# lvds_transceiver.net
KiCad netlist of a schematic drawn in Altium Designer
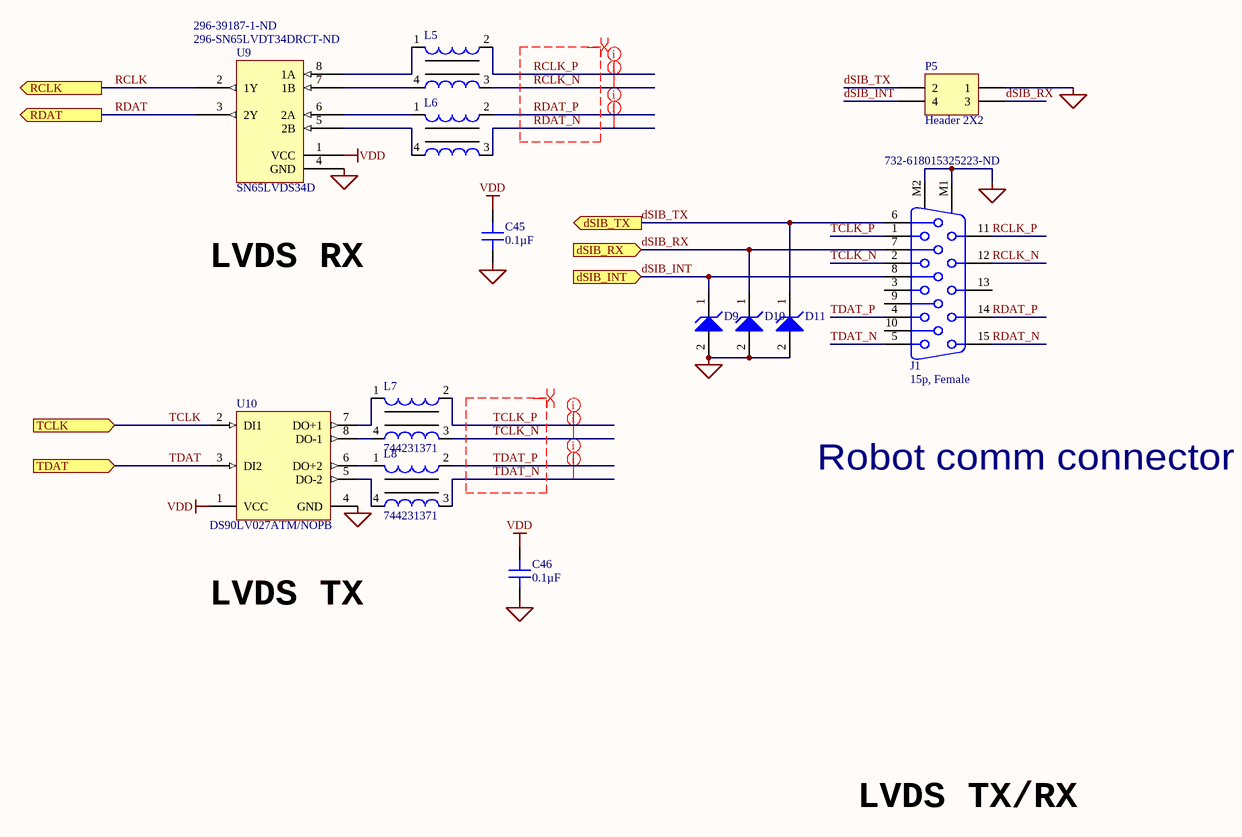
[diagram p0: lvds_transceiver.SchDoc]

(export (version "E")
  (design (tool "Eeschema 10.0.6"))
  (components
    (comp (ref "C45")
      (value "0.1µF")
      (footprint "FP-GRM155-0_05-IPC_B")
      (description "CAP CER 0.1UF 25V X7R 0402")
      (fields (field (name "PART NUMBER") "04023C104KAT2A") (field (name "MANUFACTURER") "AVX Corporation"))
      (libsource (lib "Celestial Altium Library - altium_library") (part "Capacitor"))
    )
    (comp (ref "C46")
      (value "0.1µF")
      (footprint "FP-GRM155-0_05-IPC_B")
      (description "CAP CER 0.1UF 25V X7R 0402")
      (fields (field (name "PART NUMBER") "04023C104KAT2A") (field (name "MANUFACTURER") "AVX Corporation"))
      (libsource (lib "Celestial Altium Library - altium_library") (part "Capacitor"))
    )
    (comp (ref "D9")
      (value "ESD9L3.3ST5G")
      (footprint "ONSC-SOD-923-2-514AB-01_V")
      (fields (field (name "MANUFACTURER") "On Semiconductor"))
      (libsource (lib "Altium Content Vault") (part "ONSC-K1A2-2"))
    )
    (comp (ref "D10")
      (value "ESD9L3.3ST5G")
      (footprint "ONSC-SOD-923-2-514AB-01_V")
      (fields (field (name "MANUFACTURER") "On Semiconductor"))
      (libsource (lib "Altium Content Vault") (part "ONSC-K1A2-2"))
    )
    (comp (ref "D11")
      (value "ESD9L3.3ST5G")
      (footprint "ONSC-SOD-923-2-514AB-01_V")
      (fields (field (name "MANUFACTURER") "On Semiconductor"))
      (libsource (lib "Altium Content Vault") (part "ONSC-K1A2-2"))
    )
    (comp (ref "J1")
      (value "15p, Female")
      (footprint "618015325223")
      (description "WR-DSUB Female High Density Angled PCB Connector without Hex Screw, 15p")
      (fields
        (field (name "PARTNUMBER") "618015325223")
        (field (name "SUPPLIER PART NUMBER 1") "732-618015325223-ND")
        (field (name "MANUFACTURER") "Wurth Electronics")
        (field (name "PUBLISHER") "Wurth Elektronik")
      )
      (libsource (lib "dvrk-s-pwm") (part "618015325223"))
    )
    (comp (ref "L5")
      (value "744231371")
      (footprint "WE-CNSW-0805")
      (description "SMD Common Mode Noise Suppressor WE-CNSW, Z = 370 Ohm")
      (libsource (lib "Altium Content Vault") (part "PAS-IND-INDUCTOR-4A"))
    )
    (comp (ref "L6")
      (value "744231371")
      (footprint "WE-CNSW-0805")
      (description "SMD Common Mode Noise Suppressor WE-CNSW, Z = 370 Ohm")
      (libsource (lib "Altium Content Vault") (part "PAS-IND-INDUCTOR-4A"))
    )
    (comp (ref "L7")
      (value "744231371")
      (footprint "WE-CNSW-0805")
      (description "SMD Common Mode Noise Suppressor WE-CNSW, Z = 370 Ohm")
      (libsource (lib "Altium Content Vault") (part "PAS-IND-INDUCTOR-4A"))
    )
    (comp (ref "L8")
      (value "744231371")
      (footprint "WE-CNSW-0805")
      (description "SMD Common Mode Noise Suppressor WE-CNSW, Z = 370 Ohm")
      (libsource (lib "Altium Content Vault") (part "PAS-IND-INDUCTOR-4A"))
    )
    (comp (ref "P5")
      (value "Header 2X2")
      (footprint "DF11-4DP-2DSA")
      (description "Header, 2-Pin, Dual row")
      (fields (field (name "PUBLISHER") "Altium Limited"))
      (libsource (lib "Miscellaneous Connectors") (part "Header 2X2"))
    )
    (comp (ref "U9")
      (value "SN65LVDS34D")
      (footprint "SOIC127P600X175-8N")
      (description "LVDS Receiver 8-Pin SOIC T/R")
      (fields
        (field (name "MANUFACTURER") "Texas Instruments")
        (field (name "MANUFACTURER PART NUMBER") "SN65LVDS34DR")
        (field (name "SUPPLIER PART NUMBER 1") "296-SN65LVDT34DRCT-ND")
        (field (name "SUPPLIER PART NUMBER 2") "296-39187-1-ND")
      )
      (libsource (lib "dvrk-s-comm") (part "SN65LVDS34D"))
    )
    (comp (ref "U10")
      (value "DS90LV027ATM/NOPB")
      (footprint "D0008A_L")
      (description "LVDS Dual High Speed Differential Driver, 8-pin Narrow SOIC, Pb-Free")
      (fields (field (name "MANUFACTURER") "Texas Instruments"))
      (libsource (lib "Altium Content Vault") (part "IN-LNDRV-DS90LV027AHM"))
    )
  )
  (nets
    (net (code "1") (name "/RCLK") (class "Default")
      (node (ref "U9") (pin "2") (pinfunction "1Y_2") (pintype "output"))
    )
    (net (code "2") (name "/RCLK_N") (class "Default")
      (node (ref "J1") (pin "12") (pinfunction "12_12") (pintype "passive"))
      (node (ref "L5") (pin "3") (pinfunction "3_3") (pintype "passive"))
    )
    (net (code "3") (name "/RCLK_P") (class "Default")
      (node (ref "J1") (pin "11") (pinfunction "11_11") (pintype "passive"))
      (node (ref "L5") (pin "2") (pinfunction "2_2") (pintype "passive"))
    )
    (net (code "4") (name "/RDAT") (class "Default")
      (node (ref "U9") (pin "3") (pinfunction "2Y_3") (pintype "output"))
    )
    (net (code "5") (name "/RDAT_N") (class "Default")
      (node (ref "J1") (pin "15") (pinfunction "15_15") (pintype "passive"))
      (node (ref "L6") (pin "3") (pinfunction "3_3") (pintype "passive"))
    )
    (net (code "6") (name "/RDAT_P") (class "Default")
      (node (ref "J1") (pin "14") (pinfunction "14_14") (pintype "passive"))
      (node (ref "L6") (pin "2") (pinfunction "2_2") (pintype "passive"))
    )
    (net (code "7") (name "/TCLK") (class "Default")
      (node (ref "U10") (pin "2") (pinfunction "DI1_2") (pintype "input"))
    )
    (net (code "8") (name "/TCLK_N") (class "Default")
      (node (ref "J1") (pin "2") (pinfunction "2_2") (pintype "passive"))
      (node (ref "L7") (pin "3") (pinfunction "3_3") (pintype "passive"))
    )
    (net (code "9") (name "/TCLK_P") (class "Default")
      (node (ref "J1") (pin "1") (pinfunction "1_1") (pintype "passive"))
      (node (ref "L7") (pin "2") (pinfunction "2_2") (pintype "passive"))
    )
    (net (code "10") (name "/TDAT") (class "Default")
      (node (ref "U10") (pin "3") (pinfunction "DI2_3") (pintype "input"))
    )
    (net (code "11") (name "/TDAT_N") (class "Default")
      (node (ref "J1") (pin "5") (pinfunction "5_5") (pintype "passive"))
      (node (ref "L8") (pin "3") (pinfunction "3_3") (pintype "passive"))
    )
    (net (code "12") (name "/TDAT_P") (class "Default")
      (node (ref "J1") (pin "4") (pinfunction "4_4") (pintype "passive"))
      (node (ref "L8") (pin "2") (pinfunction "2_2") (pintype "passive"))
    )
    (net (code "13") (name "/dSIB_INT") (class "Default")
      (node (ref "D9") (pin "1") (pinfunction "K_1") (pintype "passive"))
      (node (ref "J1") (pin "8") (pinfunction "8_8") (pintype "passive"))
      (node (ref "P5") (pin "4") (pinfunction "4_4") (pintype "passive"))
    )
    (net (code "14") (name "/dSIB_RX") (class "Default")
      (node (ref "D10") (pin "1") (pinfunction "K_1") (pintype "passive"))
      (node (ref "J1") (pin "7") (pinfunction "7_7") (pintype "passive"))
      (node (ref "P5") (pin "3") (pinfunction "3_3") (pintype "passive"))
    )
    (net (code "15") (name "/dSIB_TX") (class "Default")
      (node (ref "D11") (pin "1") (pinfunction "K_1") (pintype "passive"))
      (node (ref "J1") (pin "6") (pinfunction "6_6") (pintype "passive"))
      (node (ref "P5") (pin "2") (pinfunction "2_2") (pintype "passive"))
    )
    (net (code "16") (name "GND") (class "Default")
      (node (ref "C45") (pin "1") (pinfunction "1_1") (pintype "passive"))
      (node (ref "C46") (pin "1") (pinfunction "1_1") (pintype "passive"))
      (node (ref "D10") (pin "2") (pinfunction "A_2") (pintype "passive"))
      (node (ref "D11") (pin "2") (pinfunction "A_2") (pintype "passive"))
      (node (ref "D9") (pin "2") (pinfunction "A_2") (pintype "passive"))
      (node (ref "J1") (pin "M1") (pinfunction "M1_M1") (pintype "passive"))
      (node (ref "J1") (pin "M2") (pinfunction "M2_M2") (pintype "passive"))
      (node (ref "P5") (pin "1") (pinfunction "1_1") (pintype "passive"))
      (node (ref "U10") (pin "4") (pinfunction "GND_4") (pintype "power_in"))
      (node (ref "U9") (pin "4") (pinfunction "GND_4") (pintype "power_in"))
    )
    (net (code "17") (name "Net-(U9-1A)") (class "Default")
      (node (ref "L5") (pin "1") (pinfunction "1_1") (pintype "passive"))
      (node (ref "U9") (pin "8") (pinfunction "1A_8") (pintype "input"))
    )
    (net (code "18") (name "Net-(U9-1B)") (class "Default")
      (node (ref "L5") (pin "4") (pinfunction "4_4") (pintype "passive"))
      (node (ref "U9") (pin "7") (pinfunction "1B_7") (pintype "input"))
    )
    (net (code "19") (name "Net-(U9-2A)") (class "Default")
      (node (ref "L6") (pin "1") (pinfunction "1_1") (pintype "passive"))
      (node (ref "U9") (pin "6") (pinfunction "2A_6") (pintype "input"))
    )
    (net (code "20") (name "Net-(U9-2B)") (class "Default")
      (node (ref "L6") (pin "4") (pinfunction "4_4") (pintype "passive"))
      (node (ref "U9") (pin "5") (pinfunction "2B_5") (pintype "input"))
    )
    (net (code "21") (name "Net-(U10-DO+1)") (class "Default")
      (node (ref "L7") (pin "1") (pinfunction "1_1") (pintype "passive"))
      (node (ref "U10") (pin "7") (pinfunction "DO+1_7") (pintype "output"))
    )
    (net (code "22") (name "Net-(U10-DO+2)") (class "Default")
      (node (ref "L8") (pin "1") (pinfunction "1_1") (pintype "passive"))
      (node (ref "U10") (pin "6") (pinfunction "DO+2_6") (pintype "output"))
    )
    (net (code "23") (name "Net-(U10-DO-1)") (class "Default")
      (node (ref "L7") (pin "4") (pinfunction "4_4") (pintype "passive"))
      (node (ref "U10") (pin "8") (pinfunction "DO-1_8") (pintype "output"))
    )
    (net (code "24") (name "Net-(U10-DO-2)") (class "Default")
      (node (ref "L8") (pin "4") (pinfunction "4_4") (pintype "passive"))
      (node (ref "U10") (pin "5") (pinfunction "DO-2_5") (pintype "output"))
    )
    (net (code "25") (name "VDD") (class "Default")
      (node (ref "C45") (pin "2") (pinfunction "2_2") (pintype "passive"))
      (node (ref "C46") (pin "2") (pinfunction "2_2") (pintype "passive"))
      (node (ref "U10") (pin "1") (pinfunction "VCC_1") (pintype "power_in"))
      (node (ref "U9") (pin "1") (pinfunction "VCC_1") (pintype "power_in"))
    )
    (net (code "26") (name "unconnected-(J1-Pad3)") (class "Default")
      (node (ref "J1") (pin "3") (pinfunction "3_3") (pintype "passive"))
    )
    (net (code "27") (name "unconnected-(J1-Pad9)") (class "Default")
      (node (ref "J1") (pin "9") (pinfunction "9_9") (pintype "passive"))
    )
    (net (code "28") (name "unconnected-(J1-Pad10)") (class "Default")
      (node (ref "J1") (pin "10") (pinfunction "10_10") (pintype "passive"))
    )
    (net (code "29") (name "unconnected-(J1-Pad13)") (class "Default")
      (node (ref "J1") (pin "13") (pinfunction "13_13") (pintype "passive"))
    )
  )
)
